# stroboscope.net
KiCad netlist of a schematic drawn in EAGLE
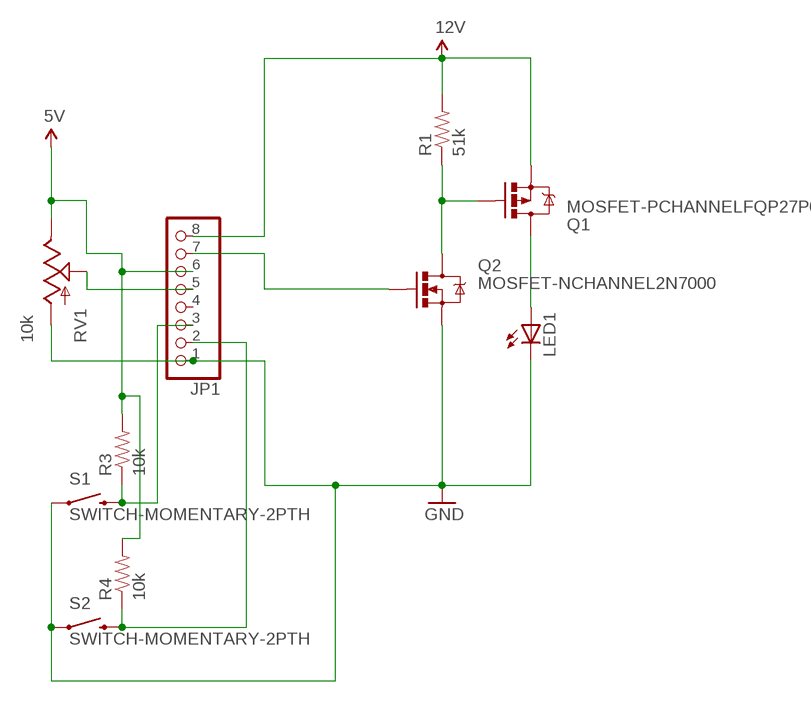
[diagram p0: schematic, sheet 1]

(export (version "E")
  (design (tool "Eeschema 10.0.6"))
  (components
    (comp (ref "JP1")
      (value "PINHD-1X8BIG")
      (footprint "eagle-import:1X08-BIG")
      (libsource (lib "eagle-import") (part "PINHD-1X8BIG"))
    )
    (comp (ref "LED1")
      (value "LEDSQR2X5")
      (footprint "eagle-import:LED2X5")
      (libsource (lib "eagle-import") (part "LEDSQR2X5"))
    )
    (comp (ref "Q1")
      (value "MOSFET-PCHANNELFQP27P06")
      (footprint "eagle-import:TO220V")
      (libsource (lib "eagle-import") (part "MOSFET-PCHANNELFQP27P06"))
    )
    (comp (ref "Q2")
      (value "MOSFET-NCHANNEL2N7000")
      (footprint "eagle-import:TO-92")
      (libsource (lib "eagle-import") (part "MOSFET-NCHANNEL2N7000"))
    )
    (comp (ref "R1")
      (value "51k")
      (footprint "eagle-import:AXIAL-0.4")
      (libsource (lib "eagle-import") (part "RESISTORPTH-1/4W"))
    )
    (comp (ref "R3")
      (value "10k")
      (footprint "eagle-import:AXIAL-0.4")
      (libsource (lib "eagle-import") (part "RESISTORPTH-1/4W"))
    )
    (comp (ref "R4")
      (value "10k")
      (footprint "eagle-import:AXIAL-0.4")
      (libsource (lib "eagle-import") (part "RESISTORPTH-1/4W"))
    )
    (comp (ref "RV1")
      (value "10k")
      (footprint "eagle-import:ALPS_POT")
      (libsource (lib "eagle-import") (part "POT"))
    )
    (comp (ref "S1")
      (value "SWITCH-MOMENTARY-2PTH")
      (footprint "eagle-import:TACTILE-PTH")
      (libsource (lib "eagle-import") (part "SWITCH-MOMENTARY-2PTH"))
    )
    (comp (ref "S2")
      (value "SWITCH-MOMENTARY-2PTH")
      (footprint "eagle-import:TACTILE-PTH")
      (libsource (lib "eagle-import") (part "SWITCH-MOMENTARY-2PTH"))
    )
  )
  (nets
    (net (code "1") (name "5V") (class "Default")
      (node (ref "JP1") (pin "6") (pinfunction "6_6") (pintype "passive"))
      (node (ref "R3") (pin "P$2") (pinfunction "2_P$2") (pintype "passive"))
      (node (ref "R4") (pin "P$2") (pinfunction "2_P$2") (pintype "passive"))
      (node (ref "RV1") (pin "P$1") (pinfunction "E_P$1") (pintype "passive"))
    )
    (net (code "2") (name "12V") (class "Default")
      (node (ref "JP1") (pin "8") (pinfunction "8_8") (pintype "passive"))
      (node (ref "Q1") (pin "3") (pinfunction "S_3") (pintype "passive"))
      (node (ref "R1") (pin "P$2") (pinfunction "2_P$2") (pintype "passive"))
    )
    (net (code "3") (name "GND") (class "Default")
      (node (ref "JP1") (pin "1") (pinfunction "1_1") (pintype "passive"))
      (node (ref "LED1") (pin "K") (pinfunction "C_K") (pintype "passive"))
      (node (ref "Q2") (pin "1") (pinfunction "S_1") (pintype "passive"))
      (node (ref "RV1") (pin "P$3") (pinfunction "A_P$3") (pintype "passive"))
      (node (ref "S1") (pin "1") (pinfunction "1_1") (pintype "passive"))
      (node (ref "S2") (pin "1") (pinfunction "1_1") (pintype "passive"))
    )
    (net (code "4") (name "Net-(Q1-D)") (class "Default")
      (node (ref "LED1") (pin "A") (pinfunction "A_A") (pintype "passive"))
      (node (ref "Q1") (pin "2") (pinfunction "D_2") (pintype "passive"))
    )
    (net (code "5") (name "Net-(Q1-G)") (class "Default")
      (node (ref "Q1") (pin "1") (pinfunction "G_1") (pintype "passive"))
      (node (ref "Q2") (pin "3") (pinfunction "D_3") (pintype "passive"))
      (node (ref "R1") (pin "P$1") (pinfunction "1_P$1") (pintype "passive"))
    )
    (net (code "6") (name "Net-(Q2-G)") (class "Default")
      (node (ref "JP1") (pin "7") (pinfunction "7_7") (pintype "passive"))
      (node (ref "Q2") (pin "2") (pinfunction "G_2") (pintype "passive"))
    )
    (net (code "7") (name "Net-(R3-1)") (class "Default")
      (node (ref "JP1") (pin "3") (pinfunction "3_3") (pintype "passive"))
      (node (ref "R3") (pin "P$1") (pinfunction "1_P$1") (pintype "passive"))
      (node (ref "S1") (pin "3") (pinfunction "2_3") (pintype "passive"))
    )
    (net (code "8") (name "Net-(R4-1)") (class "Default")
      (node (ref "JP1") (pin "2") (pinfunction "2_2") (pintype "passive"))
      (node (ref "R4") (pin "P$1") (pinfunction "1_P$1") (pintype "passive"))
      (node (ref "S2") (pin "3") (pinfunction "2_3") (pintype "passive"))
    )
    (net (code "9") (name "Net-(RV1-S)") (class "Default")
      (node (ref "JP1") (pin "5") (pinfunction "5_5") (pintype "passive"))
      (node (ref "RV1") (pin "P$2") (pinfunction "S_P$2") (pintype "passive"))
    )
    (net (code "10") (name "unconnected-(JP1-Pad4)") (class "Default")
      (node (ref "JP1") (pin "4") (pinfunction "4_4") (pintype "passive"))
    )
  )
)
